# Supply.net
KiCad netlist of a schematic drawn in Altium Designer
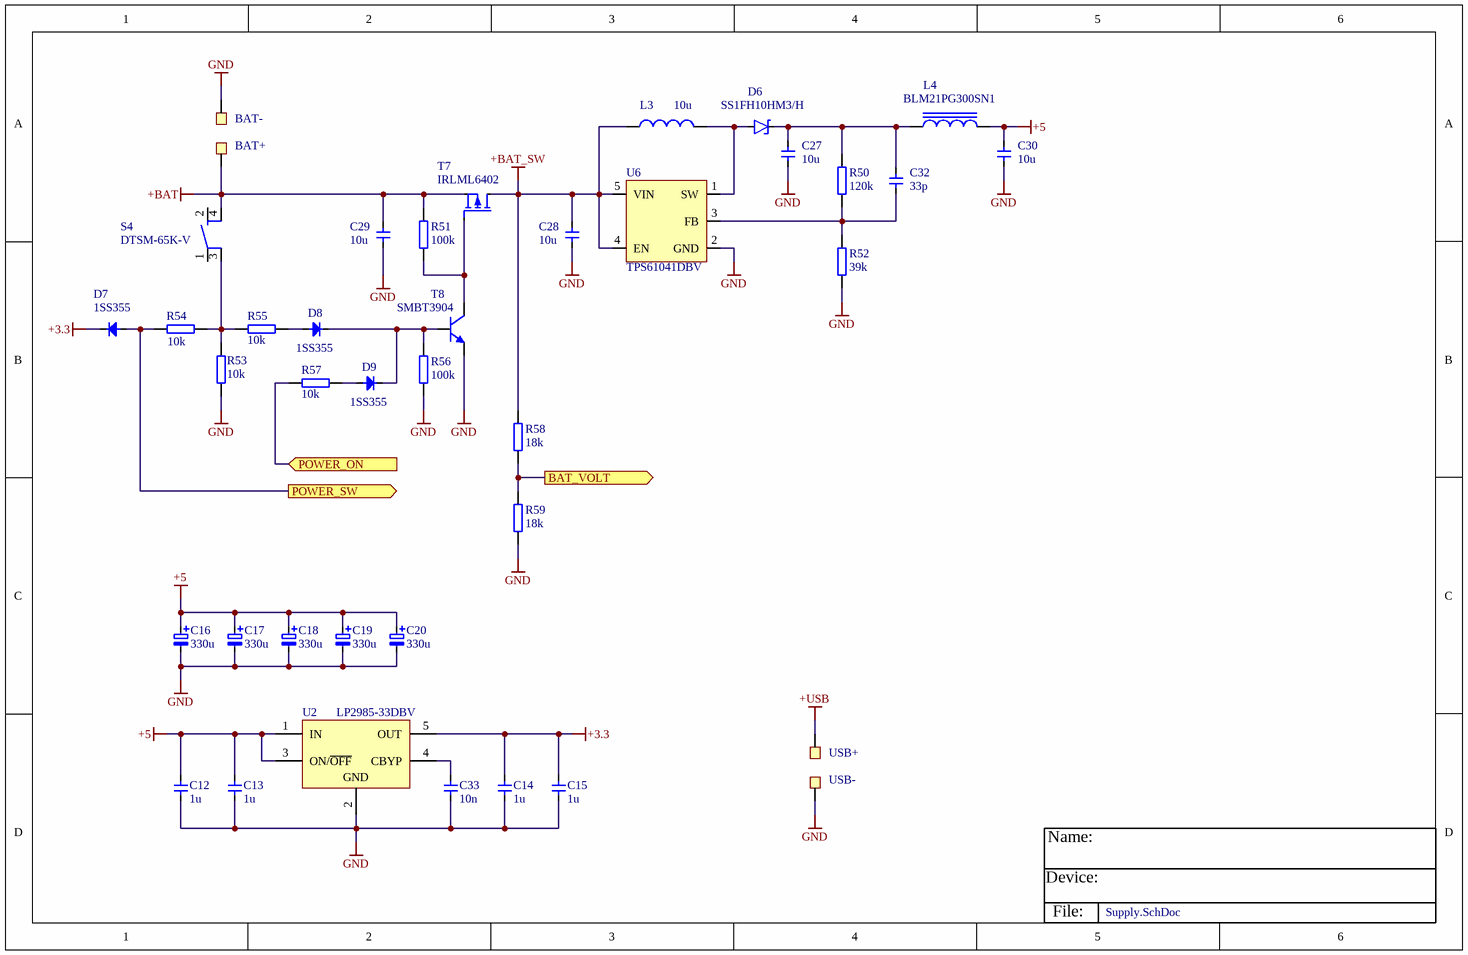
[diagram p0: Supply.SchDoc]

(export (version "E")
  (design (tool "Eeschema 10.0.6"))
  (components
    (comp (ref "BAT+")
      (value "PAD")
      (footprint "PAD_SMD_2x4")
      (description "CON;")
      (libsource (lib "") (part "CON1_1"))
    )
    (comp (ref "BAT-")
      (value "PAD")
      (footprint "PAD_SMD_2x4")
      (description "CON;")
      (libsource (lib "SONEL_all") (part "CON1"))
    )
    (comp (ref "C12")
      (value "1u")
      (footprint "C0805")
      (description "C; capacitor")
      (libsource (lib "SONEL_all") (part "C"))
    )
    (comp (ref "C13")
      (value "1u")
      (footprint "C0805")
      (description "C; capacitor")
      (libsource (lib "SONEL_all") (part "C"))
    )
    (comp (ref "C14")
      (value "1u")
      (footprint "C0805")
      (description "C; capacitor")
      (libsource (lib "SONEL_all") (part "C"))
    )
    (comp (ref "C15")
      (value "1u")
      (footprint "C0805")
      (description "C; capacitor")
      (libsource (lib "SONEL_all") (part "C"))
    )
    (comp (ref "C16")
      (value "330u")
      (footprint "D")
      (description "C; Polarized Capacitor")
      (libsource (lib "SONEL_all") (part "C_pol"))
    )
    (comp (ref "C17")
      (value "330u")
      (footprint "D")
      (description "C; Polarized Capacitor")
      (libsource (lib "SONEL_all") (part "C_pol"))
    )
    (comp (ref "C18")
      (value "330u")
      (footprint "D")
      (description "C; Polarized Capacitor")
      (libsource (lib "SONEL_all") (part "C_pol"))
    )
    (comp (ref "C19")
      (value "330u")
      (footprint "D")
      (description "C; Polarized Capacitor")
      (libsource (lib "SONEL_all") (part "C_pol"))
    )
    (comp (ref "C20")
      (value "330u")
      (footprint "D")
      (description "C; Polarized Capacitor")
      (libsource (lib "SONEL_all") (part "C_pol"))
    )
    (comp (ref "C27")
      (value "10u")
      (footprint "C0805")
      (description "C; capacitor")
      (libsource (lib "SONEL_all") (part "C"))
    )
    (comp (ref "C28")
      (value "10u")
      (footprint "C0805")
      (description "C; capacitor")
      (libsource (lib "SONEL_all") (part "C"))
    )
    (comp (ref "C29")
      (value "10u")
      (footprint "C0805")
      (description "C; capacitor")
      (libsource (lib "SONEL_all") (part "C"))
    )
    (comp (ref "C30")
      (value "10u")
      (footprint "C0805")
      (description "C; capacitor")
      (libsource (lib "SONEL_all") (part "C"))
    )
    (comp (ref "C32")
      (value "33p")
      (footprint "C0805")
      (description "C; capacitor")
      (libsource (lib "SONEL_all") (part "C"))
    )
    (comp (ref "C33")
      (value "10n")
      (footprint "C0805")
      (description "C; capacitor")
      (libsource (lib "SONEL_all") (part "C"))
    )
    (comp (ref "D6")
      (value "SS1FH10HM3/H")
      (footprint "DO-219AB")
      (description "DS; Schottky Power Rectifier 1A 100V")
      (libsource (lib "SONEL_all") (part "SS1FH10HM3/H"))
    )
    (comp (ref "D7")
      (value "1SS355")
      (footprint "SOD323")
      (description "D; Diode general")
      (libsource (lib "SONEL_all") (part "1SS355"))
    )
    (comp (ref "D8")
      (value "1SS355")
      (footprint "SOD323")
      (description "D; Diode general")
      (libsource (lib "SONEL_all") (part "1SS355"))
    )
    (comp (ref "D9")
      (value "1SS355")
      (footprint "SOD323")
      (description "D; Diode general")
      (libsource (lib "SONEL_all") (part "1SS355"))
    )
    (comp (ref "L3")
      (value "10u")
      (footprint "L1008")
      (description "L;")
      (libsource (lib "SONEL_all") (part "L"))
    )
    (comp (ref "L4")
      (value "BLM21PG300SN1")
      (footprint "L0805")
      (description "L;")
      (libsource (lib "SONEL_all") (part "BLM21PG300SN1"))
    )
    (comp (ref "R50")
      (value "120k")
      (footprint "R0805")
      (description "R; resistor")
      (libsource (lib "SONEL_all") (part "R"))
    )
    (comp (ref "R51")
      (value "100k")
      (footprint "R0805")
      (description "R; resistor")
      (libsource (lib "SONEL_all") (part "R"))
    )
    (comp (ref "R52")
      (value "39k")
      (footprint "R0805")
      (description "R; resistor")
      (libsource (lib "SONEL_all") (part "R"))
    )
    (comp (ref "R53")
      (value "10k")
      (footprint "R0805")
      (description "R; resistor")
      (libsource (lib "SONEL_all") (part "R"))
    )
    (comp (ref "R54")
      (value "10k")
      (footprint "R0805")
      (description "R; resistor")
      (libsource (lib "SONEL_all") (part "R"))
    )
    (comp (ref "R55")
      (value "10k")
      (footprint "R0805")
      (description "R; resistor")
      (libsource (lib "SONEL_all") (part "R"))
    )
    (comp (ref "R56")
      (value "100k")
      (footprint "R0805")
      (description "R; resistor")
      (libsource (lib "SONEL_all") (part "R"))
    )
    (comp (ref "R57")
      (value "10k")
      (footprint "R0805")
      (description "R; resistor")
      (libsource (lib "SONEL_all") (part "R"))
    )
    (comp (ref "R58")
      (value "18k")
      (footprint "R0805")
      (description "R; resistor")
      (libsource (lib "SONEL_all") (part "R"))
    )
    (comp (ref "R59")
      (value "18k")
      (footprint "R0805")
      (description "R; resistor")
      (libsource (lib "SONEL_all") (part "R"))
    )
    (comp (ref "S4")
      (value "DTSM-65K-V")
      (footprint "DTSM-65K-V")
      (description "SWITCH; TACT switch, 6x6, h=9.5mm")
      (libsource (lib "SONEL_all") (part "DTSM-65K-V"))
    )
    (comp (ref "T7")
      (value "IRLML6402")
      (footprint "MICRO3")
      (description "T_M_P; P-Channel MOSFET")
      (libsource (lib "SONEL_all") (part "IRLML6402"))
    )
    (comp (ref "T8")
      (value "SMBT3904")
      (footprint "SOT23J")
      (description "T_NPN; Bipolar Transistor")
      (libsource (lib "SONEL_all") (part "SMBT3904"))
    )
    (comp (ref "U2")
      (value "LP2985-33DBV")
      (footprint "DBV_R-PDSO-G5")
      (description "LDO; Micropower 150 mA Low-Noise Ultra Low-Dropout Regulator in  SOT-23 and micro SMD Packages")
      (fields
        (field (name "PARTNUMBER") "LP2985AIM5-3.3")
        (field (name "MANUFACTURER") "National Semiconductor")
        (field (name "PUBLISHER") "Altium Limited")
      )
      (libsource (lib "SONEL_all") (part "LP2985-33DBV"))
    )
    (comp (ref "U6")
      (value "TPS61041DBV")
      (footprint "DBV_R-PDSO-G5")
      (description "DC/DC; 28V, 250mA Switch Boost Converter for LCD and White LED Applications")
      (libsource (lib "SONEL_all") (part "TPS61041DBV"))
    )
    (comp (ref "USB+")
      (value "PAD")
      (footprint "PAD_SMD_2x4")
      (description "CON;")
      (libsource (lib "SONEL_all") (part "CON1"))
    )
    (comp (ref "USB-")
      (value "PAD")
      (footprint "PAD_SMD_2x4")
      (description "CON;")
      (libsource (lib "") (part "CON1_1"))
    )
  )
  (nets
    (net (code "1") (name "+3.3") (class "Default")
      (node (ref "C14") (pin "2") (pintype "passive"))
      (node (ref "C15") (pin "2") (pintype "passive"))
      (node (ref "D7") (pin "K") (pinfunction "K_K") (pintype "passive"))
      (node (ref "U2") (pin "5") (pinfunction "OUT_5") (pintype "power_in"))
    )
    (net (code "2") (name "+5") (class "Default")
      (node (ref "C12") (pin "2") (pintype "passive"))
      (node (ref "C13") (pin "2") (pintype "passive"))
      (node (ref "C16") (pin "+") (pinfunction "1_+") (pintype "passive"))
      (node (ref "C17") (pin "+") (pinfunction "1_+") (pintype "passive"))
      (node (ref "C18") (pin "+") (pinfunction "1_+") (pintype "passive"))
      (node (ref "C19") (pin "+") (pinfunction "1_+") (pintype "passive"))
      (node (ref "C20") (pin "+") (pinfunction "1_+") (pintype "passive"))
      (node (ref "C30") (pin "2") (pintype "passive"))
      (node (ref "L4") (pin "2") (pinfunction "2_2") (pintype "passive"))
      (node (ref "U2") (pin "1") (pinfunction "IN_1") (pintype "power_in"))
      (node (ref "U2") (pin "3") (pinfunction "ON/~{OFF}_3") (pintype "passive"))
    )
    (net (code "3") (name "+BAT") (class "Default")
      (node (ref "BAT+") (pin "1") (pinfunction "1_1") (pintype "passive"))
      (node (ref "C29") (pin "2") (pintype "passive"))
      (node (ref "R51") (pin "1") (pintype "passive"))
      (node (ref "S4") (pin "4") (pinfunction "2_4") (pintype "passive"))
      (node (ref "T7") (pin "S") (pinfunction "S_S") (pintype "passive"))
    )
    (net (code "4") (name "+BAT_SW") (class "Default")
      (node (ref "C28") (pin "2") (pintype "passive"))
      (node (ref "L3") (pin "1") (pinfunction "1_1") (pintype "passive"))
      (node (ref "R58") (pin "1") (pintype "passive"))
      (node (ref "T7") (pin "D") (pinfunction "D_D") (pintype "passive"))
      (node (ref "U6") (pin "4") (pinfunction "EN_4") (pintype "passive"))
      (node (ref "U6") (pin "5") (pinfunction "VIN_5") (pintype "passive"))
    )
    (net (code "5") (name "+USB") (class "Default")
      (node (ref "USB+") (pin "1") (pinfunction "1_1") (pintype "passive"))
    )
    (net (code "6") (name "/BAT_VOLT") (class "Default")
      (node (ref "R58") (pin "2") (pintype "passive"))
      (node (ref "R59") (pin "1") (pintype "passive"))
    )
    (net (code "7") (name "/POWER_ON") (class "Default") (node (ref "R57") (pin "1") (pintype "passive")))
    (net (code "8") (name "/POWER_SW") (class "Default")
      (node (ref "D7") (pin "A") (pinfunction "A_A") (pintype "passive"))
      (node (ref "R54") (pin "1") (pintype "passive"))
    )
    (net (code "9") (name "GND") (class "Default")
      (node (ref "BAT-") (pin "1") (pinfunction "1_1") (pintype "passive"))
      (node (ref "C12") (pin "1") (pintype "passive"))
      (node (ref "C13") (pin "1") (pintype "passive"))
      (node (ref "C14") (pin "1") (pintype "passive"))
      (node (ref "C15") (pin "1") (pintype "passive"))
      (node (ref "C16") (pin "-") (pinfunction "2_-") (pintype "passive"))
      (node (ref "C17") (pin "-") (pinfunction "2_-") (pintype "passive"))
      (node (ref "C18") (pin "-") (pinfunction "2_-") (pintype "passive"))
      (node (ref "C19") (pin "-") (pinfunction "2_-") (pintype "passive"))
      (node (ref "C20") (pin "-") (pinfunction "2_-") (pintype "passive"))
      (node (ref "C27") (pin "1") (pintype "passive"))
      (node (ref "C28") (pin "1") (pintype "passive"))
      (node (ref "C29") (pin "1") (pintype "passive"))
      (node (ref "C30") (pin "1") (pintype "passive"))
      (node (ref "C33") (pin "1") (pintype "passive"))
      (node (ref "R52") (pin "2") (pintype "passive"))
      (node (ref "R53") (pin "1") (pintype "passive"))
      (node (ref "R56") (pin "2") (pintype "passive"))
      (node (ref "R59") (pin "2") (pintype "passive"))
      (node (ref "T8") (pin "1") (pinfunction "E_1") (pintype "passive"))
      (node (ref "U2") (pin "2") (pinfunction "GND_2") (pintype "power_in"))
      (node (ref "U6") (pin "2") (pinfunction "GND_2") (pintype "passive"))
      (node (ref "USB-") (pin "1") (pinfunction "1_1") (pintype "passive"))
    )
    (net (code "10") (name "Net-(C27-Pad2)") (class "Default")
      (node (ref "C27") (pin "2") (pintype "passive"))
      (node (ref "C32") (pin "2") (pintype "passive"))
      (node (ref "D6") (pin "K") (pinfunction "K_K") (pintype "passive"))
      (node (ref "L4") (pin "1") (pinfunction "1_1") (pintype "passive"))
      (node (ref "R50") (pin "1") (pintype "passive"))
    )
    (net (code "11") (name "Net-(D8-PadA)") (class "Default")
      (node (ref "D8") (pin "A") (pinfunction "A_A") (pintype "passive"))
      (node (ref "R55") (pin "2") (pintype "passive"))
    )
    (net (code "12") (name "Net-(D9-PadA)") (class "Default")
      (node (ref "D9") (pin "A") (pinfunction "A_A") (pintype "passive"))
      (node (ref "R57") (pin "2") (pintype "passive"))
    )
    (net (code "13") (name "Net-(S4-P2)") (class "Default")
      (node (ref "R53") (pin "2") (pintype "passive"))
      (node (ref "R54") (pin "2") (pintype "passive"))
      (node (ref "R55") (pin "1") (pintype "passive"))
      (node (ref "S4") (pin "3") (pinfunction "P2_3") (pintype "passive"))
    )
    (net (code "14") (name "Net-(T8-B)") (class "Default")
      (node (ref "D8") (pin "K") (pinfunction "K_K") (pintype "passive"))
      (node (ref "D9") (pin "K") (pinfunction "K_K") (pintype "passive"))
      (node (ref "R56") (pin "1") (pintype "passive"))
      (node (ref "T8") (pin "2") (pinfunction "B_2") (pintype "passive"))
    )
    (net (code "15") (name "Net-(T8-C)") (class "Default")
      (node (ref "R51") (pin "2") (pintype "passive"))
      (node (ref "T7") (pin "G") (pinfunction "G_G") (pintype "passive"))
      (node (ref "T8") (pin "3") (pinfunction "C_3") (pintype "passive"))
    )
    (net (code "16") (name "Net-(U2-CBYP)") (class "Default")
      (node (ref "C33") (pin "2") (pintype "passive"))
      (node (ref "U2") (pin "4") (pinfunction "CBYP_4") (pintype "passive"))
    )
    (net (code "17") (name "Net-(U6-FB)") (class "Default")
      (node (ref "C32") (pin "1") (pintype "passive"))
      (node (ref "R50") (pin "2") (pintype "passive"))
      (node (ref "R52") (pin "1") (pintype "passive"))
      (node (ref "U6") (pin "3") (pinfunction "FB_3") (pintype "passive"))
    )
    (net (code "18") (name "Net-(U6-SW)") (class "Default")
      (node (ref "D6") (pin "A") (pinfunction "A_A") (pintype "passive"))
      (node (ref "L3") (pin "2") (pinfunction "2_2") (pintype "passive"))
      (node (ref "U6") (pin "1") (pinfunction "SW_1") (pintype "passive"))
    )
    (net (code "19") (name "unconnected-(S4-P1-Pad1)") (class "Default")
      (node (ref "S4") (pin "1") (pinfunction "P1_1") (pintype "passive"))
    )
    (net (code "20") (name "unconnected-(S4-S1-Pad2)") (class "Default")
      (node (ref "S4") (pin "2") (pinfunction "S1_2") (pintype "passive"))
    )
  )
)
